# gt_cam_revf.net
KiCad netlist of a schematic drawn in EAGLE
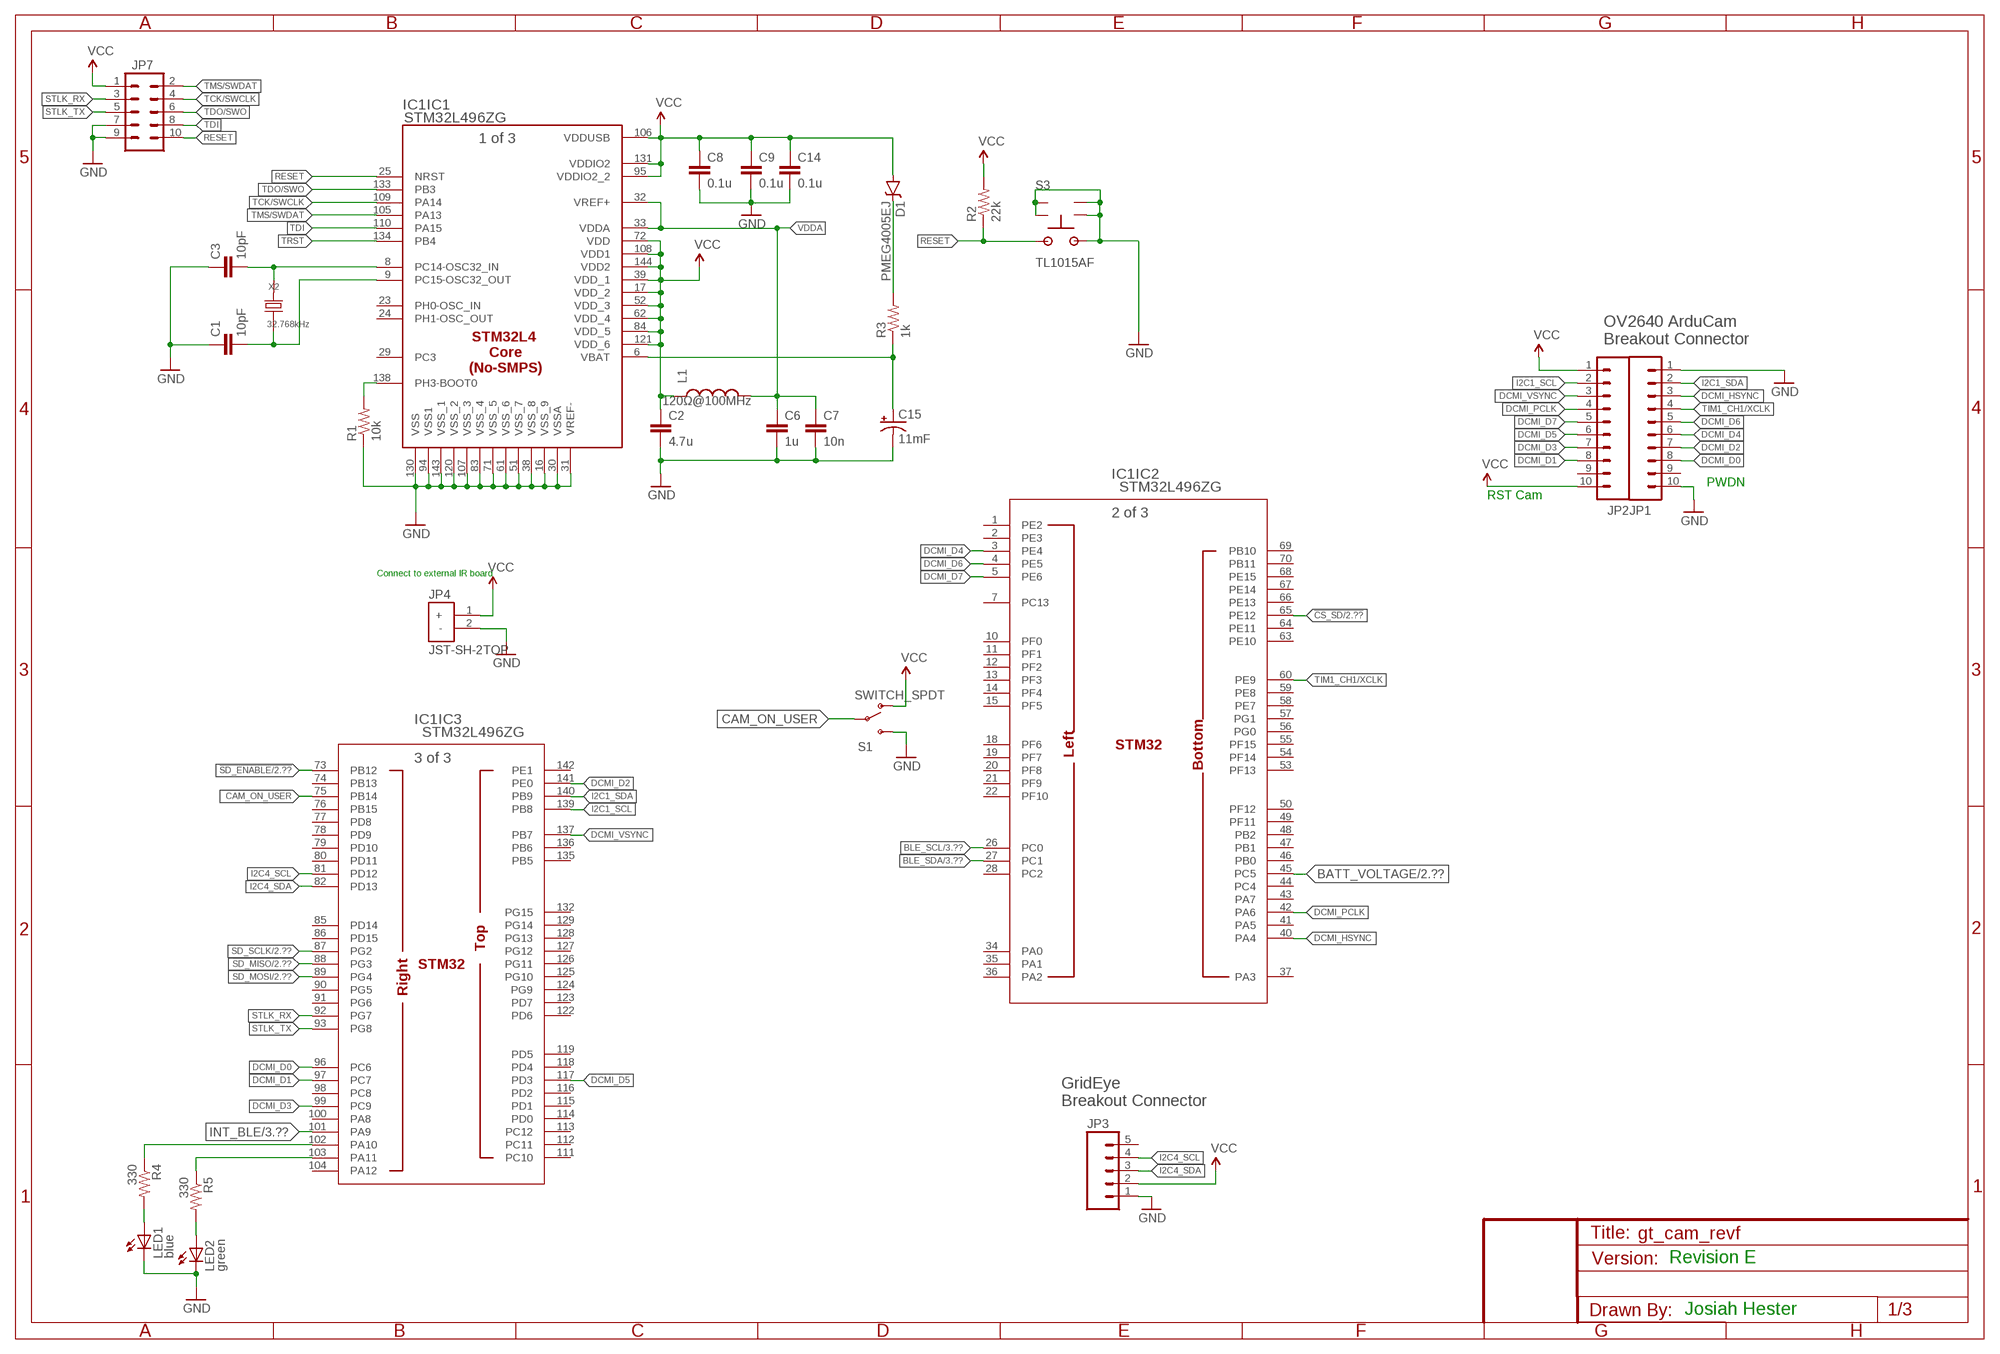
[diagram p0: schematic, sheet 1]
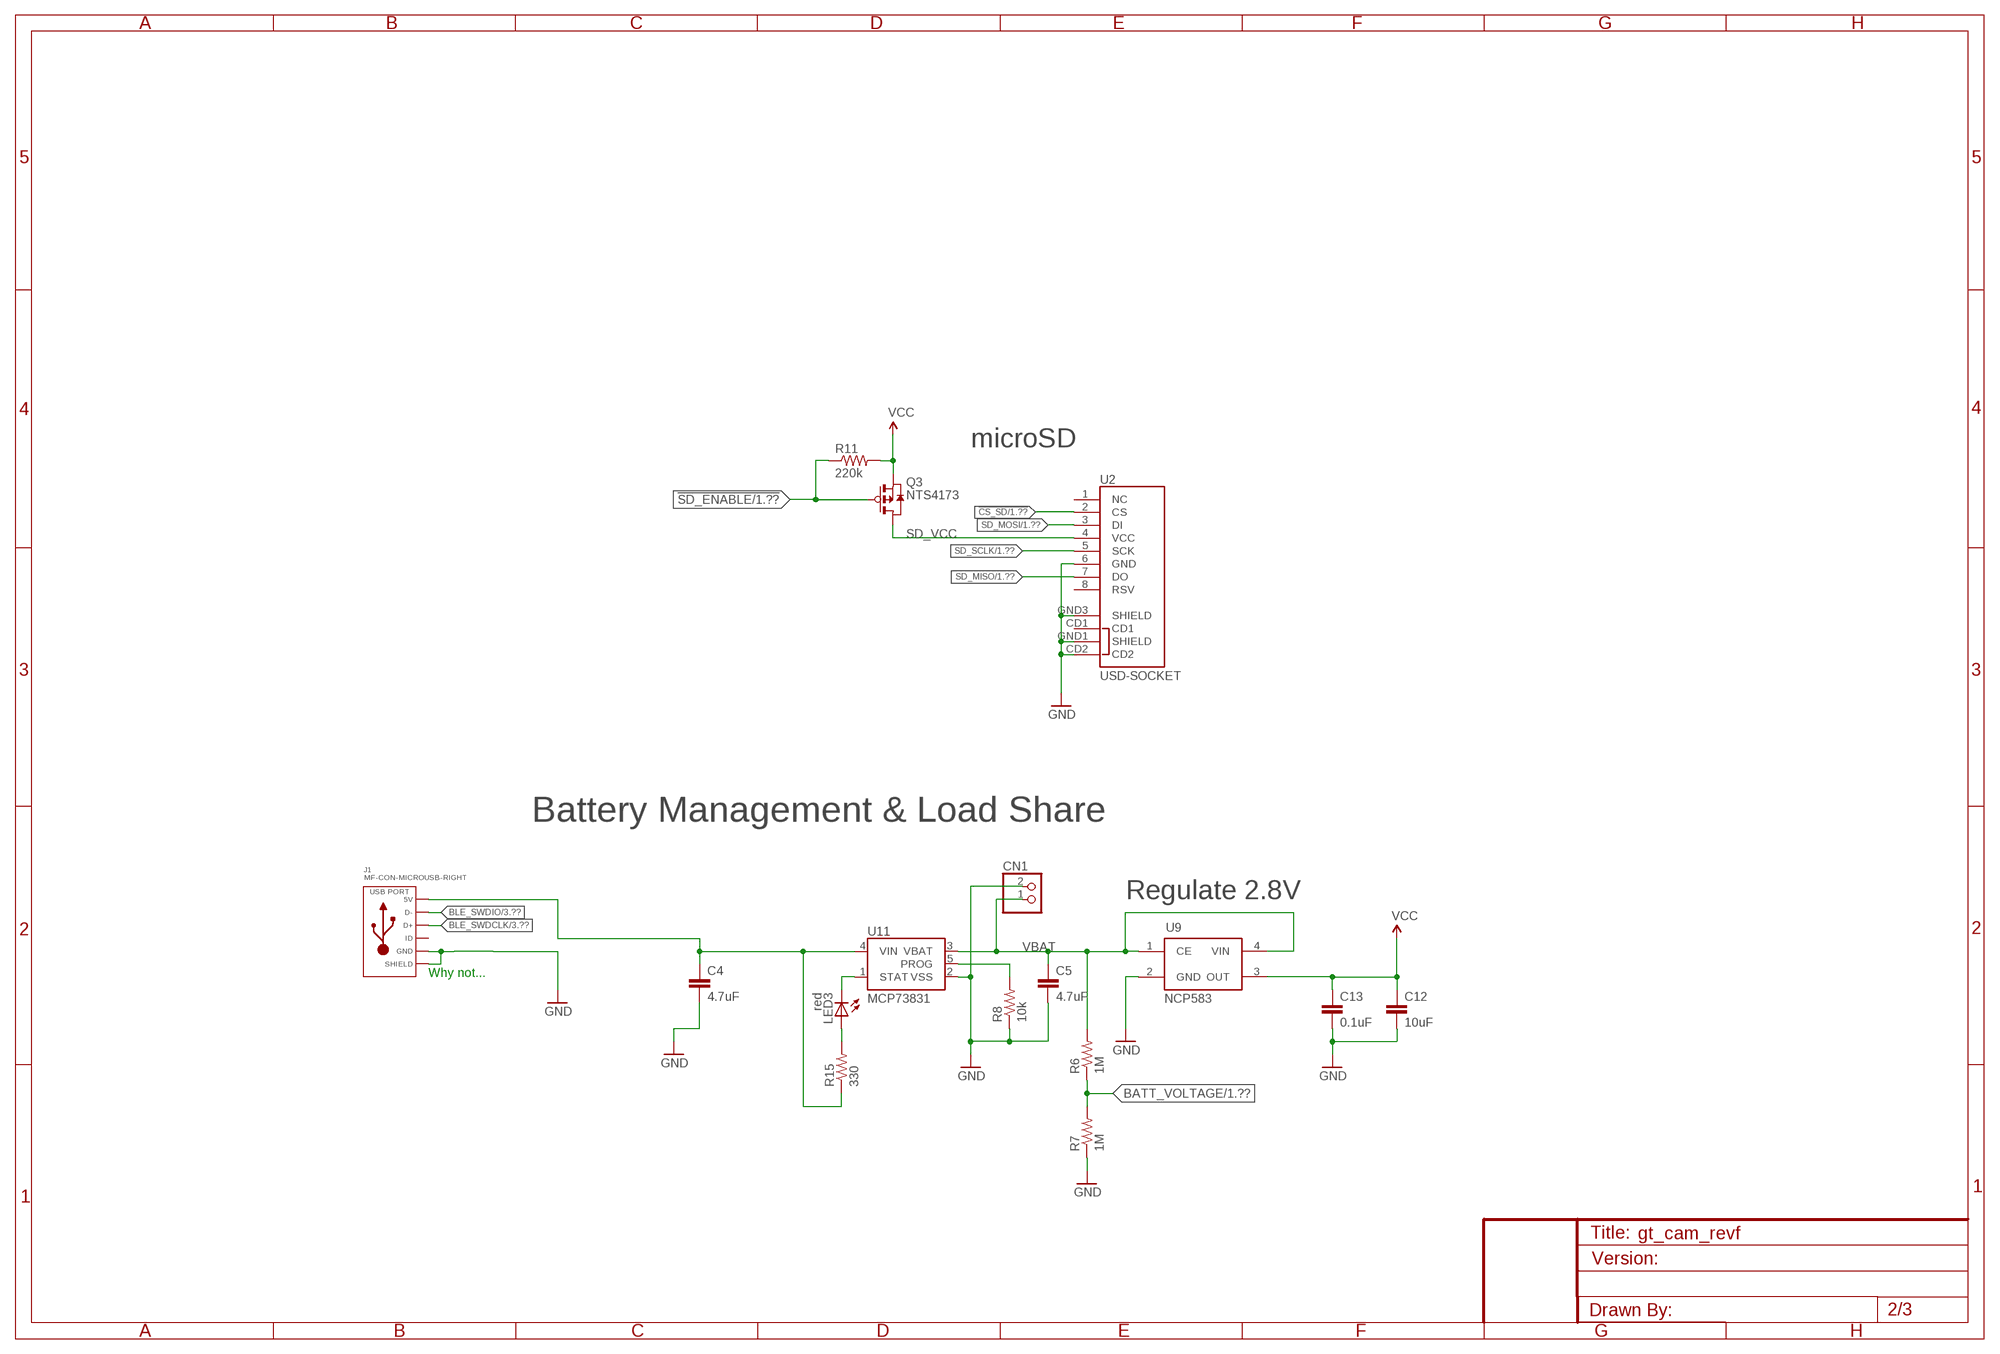
[diagram p1: schematic, sheet 2]
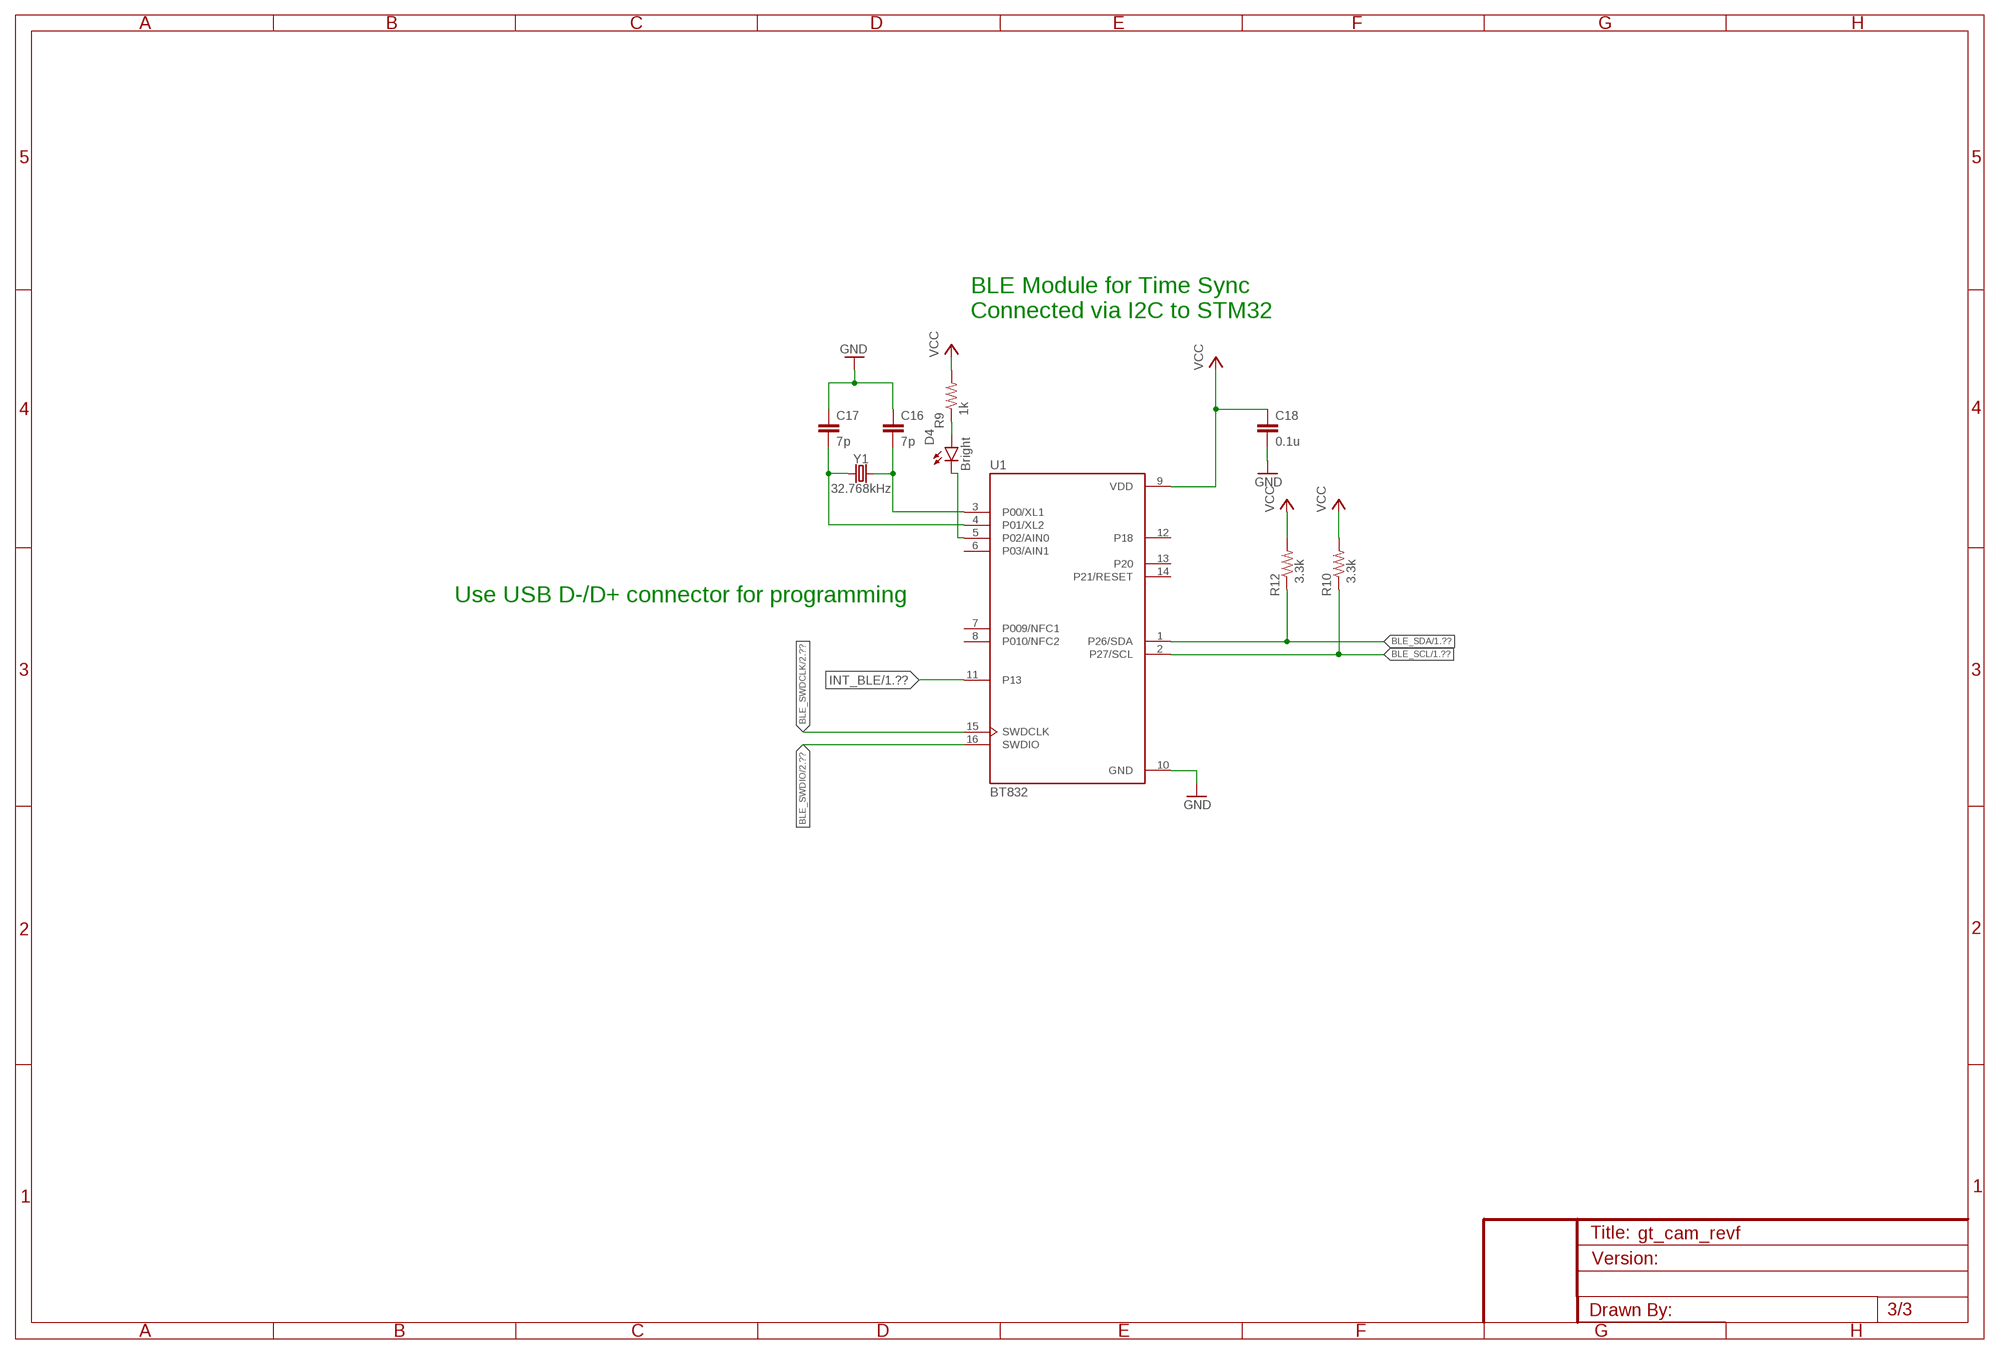
[diagram p2: schematic, sheet 3]

(export (version "E")
  (design (tool "Eeschema 10.0.6"))
  (components
    (comp (ref "C16")
      (value "7p")
      (footprint "eagle-import:0603")
      (libsource (lib "eagle-import") (part "C-EU0603"))
    )
    (comp (ref "C17")
      (value "7p")
      (footprint "eagle-import:0603")
      (libsource (lib "eagle-import") (part "C-EU0603"))
    )
    (comp (ref "C18")
      (value "0.1u")
      (footprint "eagle-import:0603")
      (libsource (lib "eagle-import") (part "C-EU0603"))
    )
    (comp (ref "D4")
      (value "Bright")
      (footprint "eagle-import:LED-0603")
      (libsource (lib "eagle-import") (part "necklace_done_LED0603"))
    )
    (comp (ref "R9")
      (value "1k")
      (footprint "eagle-import:0603")
      (libsource (lib "eagle-import") (part "R-EU0603"))
    )
    (comp (ref "R10")
      (value "3.3k")
      (footprint "eagle-import:0603")
      (libsource (lib "eagle-import") (part "R-EU0603"))
    )
    (comp (ref "R12")
      (value "3.3k")
      (footprint "eagle-import:0603")
      (libsource (lib "eagle-import") (part "R-EU0603"))
    )
    (comp (ref "U1")
      (value "BT832")
      (footprint "eagle-import:BLEMODULE_BT832")
      (fields (field (name "DIGI-KEY_PART_NUMBER") "1914-1013-1-ND") (field (name "MF") "Fanstel Corp."))
      (libsource (lib "eagle-import") (part "BT832"))
    )
    (comp (ref "Y1")
      (value "32.768kHz")
      (footprint "eagle-import:CRYSTAL-SMD-3.2X1.5MM")
      (fields (field (name "DIGI-KEY_PART_NUMBER") "SER4271CT-ND"))
      (libsource (lib "eagle-import") (part "CRYSTAL-32.768KHZSMD-3.2X1.5"))
    )
    (comp (ref "C4")
      (value "4.7uF")
      (footprint "eagle-import:0805")
      (libsource (lib "eagle-import") (part "CAP0805"))
    )
    (comp (ref "C5")
      (value "4.7uF")
      (footprint "eagle-import:0805")
      (libsource (lib "eagle-import") (part "CAP0805"))
    )
    (comp (ref "C12")
      (value "10uF")
      (footprint "eagle-import:0805")
      (libsource (lib "eagle-import") (part "CAP0805"))
    )
    (comp (ref "C13")
      (value "0.1uF")
      (footprint "eagle-import:0603")
      (libsource (lib "eagle-import") (part "C-EU0603"))
    )
    (comp (ref "CN1")
      (value "JST_2PIN-SMT-RA")
      (footprint "eagle-import:JST-PH-2-SMT-RA")
      (libsource (lib "eagle-import") (part "JST_2PIN-SMT-RA"))
    )
    (comp (ref "J1")
      (value "MF-CON-MICROUSB-RIGHT")
      (footprint "eagle-import:MICROUSB-RIGHT")
      (fields (field (name "HOUSEPART") "YES"))
      (libsource (lib "eagle-import") (part "USB_MICRO_RIGHT"))
    )
    (comp (ref "LED3")
      (value "red")
      (footprint "eagle-import:LED-0603")
      (libsource (lib "eagle-import") (part "LED0603"))
    )
    (comp (ref "Q3")
      (value "NTS4173")
      (footprint "eagle-import:SC-70-3")
      (libsource (lib "eagle-import") (part "NTS4173"))
    )
    (comp (ref "R6")
      (value "1M")
      (footprint "eagle-import:0603")
      (libsource (lib "eagle-import") (part "R-EU0603"))
    )
    (comp (ref "R7")
      (value "1M")
      (footprint "eagle-import:0603")
      (libsource (lib "eagle-import") (part "R-EU0603"))
    )
    (comp (ref "R8")
      (value "10k")
      (footprint "eagle-import:0603")
      (libsource (lib "eagle-import") (part "R-EU0603"))
    )
    (comp (ref "R11")
      (value "220k")
      (footprint "eagle-import:0603")
      (libsource (lib "eagle-import") (part "R-EU0603"))
    )
    (comp (ref "R15")
      (value "330")
      (footprint "eagle-import:0603")
      (libsource (lib "eagle-import") (part "R-EU0603"))
    )
    (comp (ref "U2")
      (value "USD-SOCKET")
      (footprint "eagle-import:MICROSD_1_1")
      (libsource (lib "eagle-import") (part "USD-SOCKET"))
    )
    (comp (ref "U9")
      (value "NCP583")
      (footprint "eagle-import:SC82-AB_1PRIMARY")
      (libsource (lib "eagle-import") (part "NCP583"))
    )
    (comp (ref "U11")
      (value "MCP73831")
      (footprint "eagle-import:SOT23-5")
      (libsource (lib "eagle-import") (part "MCP73831"))
    )
    (comp (ref "C1")
      (value "10pF")
      (footprint "eagle-import:0603")
      (libsource (lib "eagle-import") (part "C-EU0603"))
    )
    (comp (ref "C2")
      (value "4.7u")
      (footprint "eagle-import:0805")
      (libsource (lib "eagle-import") (part "CAP0805"))
    )
    (comp (ref "C3")
      (value "10pF")
      (footprint "eagle-import:0603")
      (libsource (lib "eagle-import") (part "C-EU0603"))
    )
    (comp (ref "C6")
      (value "1u")
      (footprint "eagle-import:0603")
      (libsource (lib "eagle-import") (part "C-EU0603"))
    )
    (comp (ref "C7")
      (value "10n")
      (footprint "eagle-import:0603")
      (libsource (lib "eagle-import") (part "C-EU0603"))
    )
    (comp (ref "C8")
      (value "0.1u")
      (footprint "eagle-import:0603")
      (libsource (lib "eagle-import") (part "C-EU0603"))
    )
    (comp (ref "C9")
      (value "0.1u")
      (footprint "eagle-import:0603")
      (libsource (lib "eagle-import") (part "C-EU0603"))
    )
    (comp (ref "C14")
      (value "0.1u")
      (footprint "eagle-import:0603")
      (libsource (lib "eagle-import") (part "C-EU0603"))
    )
    (comp (ref "C15")
      (value "11mF")
      (footprint "eagle-import:EIA3216")
      (libsource (lib "eagle-import") (part "CAP_POL1206"))
    )
    (comp (ref "D1")
      (value "PMEG4005EJ")
      (footprint "eagle-import:SOD-323")
      (libsource (lib "eagle-import") (part "DIODE-SCHOTTKY-PMEG4005EJ"))
    )
    (comp (ref "IC1")
      (value "STM32L496ZG")
      (footprint "eagle-import:LQFP144-20X20MM")
      (fields (field (name "DIGIKEY") "497-17999-ND"))
      (libsource (lib "eagle-import") (part "STM32L496ZG"))
    )
    (comp (ref "JP1")
      (value "M10SILK_FEMALE_PTH")
      (footprint "eagle-import:1X10")
      (libsource (lib "eagle-import") (part "M10SILK_FEMALE_PTH"))
    )
    (comp (ref "JP2")
      (value "M10SILK_FEMALE_PTH")
      (footprint "eagle-import:1X10")
      (libsource (lib "eagle-import") (part "M10SILK_FEMALE_PTH"))
    )
    (comp (ref "JP3")
      (value "M05LOCK")
      (footprint "eagle-import:1X05_LOCK")
      (libsource (lib "eagle-import") (part "M05LOCK"))
    )
    (comp (ref "JP4")
      (value "JST-SH-2TOP")
      (footprint "eagle-import:JST-SH-2-TOP")
      (libsource (lib "eagle-import") (part "JST-SH-2TOP"))
    )
    (comp (ref "JP7")
      (value "M05X21.27MM")
      (footprint "eagle-import:2X5_1.27MM")
      (libsource (lib "eagle-import") (part "M05X21.27MM"))
    )
    (comp (ref "L1")
      (value "120Ω@100MHz")
      (footprint "eagle-import:0402")
      (libsource (lib "eagle-import") (part "L-EU"))
    )
    (comp (ref "LED1")
      (value "blue")
      (footprint "eagle-import:LED-0603")
      (libsource (lib "eagle-import") (part "LED0603"))
    )
    (comp (ref "LED2")
      (value "green")
      (footprint "eagle-import:LED-0603")
      (libsource (lib "eagle-import") (part "LED0603"))
    )
    (comp (ref "R1")
      (value "10k")
      (footprint "eagle-import:0603")
      (libsource (lib "eagle-import") (part "R-EU0603"))
    )
    (comp (ref "R2")
      (value "22k")
      (footprint "eagle-import:0603")
      (libsource (lib "eagle-import") (part "R-EU0603"))
    )
    (comp (ref "R3")
      (value "1k")
      (footprint "eagle-import:0603")
      (libsource (lib "eagle-import") (part "R-EU0603"))
    )
    (comp (ref "R4")
      (value "330")
      (footprint "eagle-import:0603")
      (libsource (lib "eagle-import") (part "R-EU0603"))
    )
    (comp (ref "R5")
      (value "330")
      (footprint "eagle-import:0603")
      (libsource (lib "eagle-import") (part "R-EU0603"))
    )
    (comp (ref "S1")
      (value "SWITCH_SPDT")
      (footprint "eagle-import:EG-1213")
      (libsource (lib "eagle-import") (part "SWITCH_SPDT"))
    )
    (comp (ref "S3")
      (value "TL1015AF")
      (footprint "eagle-import:TS1015")
      (fields (field (name "MPN") "TL1015AF160QG"))
      (libsource (lib "eagle-import") (part "TL1015AF"))
    )
    (comp (ref "X2")
      (value "32.768kHz")
      (footprint "eagle-import:FC-135_1PRIMARY")
      (libsource (lib "eagle-import") (part "FC-135"))
    )
  )
  (nets
    (net (code "1") (name "BATT_VOLTAGE") (class "Default")
      (node (ref "IC1") (pin "45") (pinfunction "PC5_45") (pintype "bidirectional"))
      (node (ref "R6") (pin "1") (pinfunction "1_1") (pintype "passive"))
      (node (ref "R7") (pin "2") (pinfunction "2_2") (pintype "passive"))
    )
    (net (code "2") (name "BLE_SCL") (class "Default")
      (node (ref "IC1") (pin "26") (pinfunction "PC0_26") (pintype "bidirectional"))
      (node (ref "R10") (pin "1") (pinfunction "1_1") (pintype "passive"))
      (node (ref "U1") (pin "2") (pinfunction "P27/SCL_2") (pintype "bidirectional"))
    )
    (net (code "3") (name "BLE_SDA") (class "Default")
      (node (ref "IC1") (pin "27") (pinfunction "PC1_27") (pintype "bidirectional"))
      (node (ref "R12") (pin "1") (pinfunction "1_1") (pintype "passive"))
      (node (ref "U1") (pin "1") (pinfunction "P26/SDA_1") (pintype "bidirectional"))
    )
    (net (code "4") (name "BLE_SWDCLK") (class "Default")
      (node (ref "J1") (pin "3") (pinfunction "D+_3") (pintype "bidirectional"))
      (node (ref "U1") (pin "15") (pinfunction "SWDCLK_15") (pintype "input"))
    )
    (net (code "5") (name "BLE_SWDIO") (class "Default")
      (node (ref "J1") (pin "2") (pinfunction "D-_2") (pintype "bidirectional"))
      (node (ref "U1") (pin "16") (pinfunction "SWDIO_16") (pintype "bidirectional"))
    )
    (net (code "6") (name "CAM_ON_USER") (class "Default")
      (node (ref "IC1") (pin "75") (pinfunction "PB14_75") (pintype "bidirectional"))
      (node (ref "S1") (pin "C") (pinfunction "C_C") (pintype "passive"))
    )
    (net (code "7") (name "DCMI_D0") (class "Default")
      (node (ref "IC1") (pin "96") (pinfunction "PC6_96") (pintype "bidirectional"))
      (node (ref "JP1") (pin "8") (pinfunction "8_8") (pintype "passive"))
    )
    (net (code "8") (name "DCMI_D1") (class "Default")
      (node (ref "IC1") (pin "97") (pinfunction "PC7_97") (pintype "bidirectional"))
      (node (ref "JP2") (pin "8") (pinfunction "8_8") (pintype "passive"))
    )
    (net (code "9") (name "DCMI_D2") (class "Default")
      (node (ref "IC1") (pin "141") (pinfunction "PE0_141") (pintype "bidirectional"))
      (node (ref "JP1") (pin "7") (pinfunction "7_7") (pintype "passive"))
    )
    (net (code "10") (name "DCMI_D3") (class "Default")
      (node (ref "IC1") (pin "99") (pinfunction "PC9_99") (pintype "bidirectional"))
      (node (ref "JP2") (pin "7") (pinfunction "7_7") (pintype "passive"))
    )
    (net (code "11") (name "DCMI_D4") (class "Default")
      (node (ref "IC1") (pin "3") (pinfunction "PE4_3") (pintype "bidirectional"))
      (node (ref "JP1") (pin "6") (pinfunction "6_6") (pintype "passive"))
    )
    (net (code "12") (name "DCMI_D5") (class "Default")
      (node (ref "IC1") (pin "117") (pinfunction "PD3_117") (pintype "bidirectional"))
      (node (ref "JP2") (pin "6") (pinfunction "6_6") (pintype "passive"))
    )
    (net (code "13") (name "DCMI_D6") (class "Default")
      (node (ref "IC1") (pin "4") (pinfunction "PE5_4") (pintype "bidirectional"))
      (node (ref "JP1") (pin "5") (pinfunction "5_5") (pintype "passive"))
    )
    (net (code "14") (name "DCMI_D7") (class "Default")
      (node (ref "IC1") (pin "5") (pinfunction "PE6_5") (pintype "bidirectional"))
      (node (ref "JP2") (pin "5") (pinfunction "5_5") (pintype "passive"))
    )
    (net (code "15") (name "DCMI_HSYNC") (class "Default")
      (node (ref "IC1") (pin "40") (pinfunction "PA4_40") (pintype "bidirectional"))
      (node (ref "JP1") (pin "3") (pinfunction "3_3") (pintype "passive"))
    )
    (net (code "16") (name "DCMI_PCLK") (class "Default")
      (node (ref "IC1") (pin "42") (pinfunction "PA6_42") (pintype "bidirectional"))
      (node (ref "JP2") (pin "4") (pinfunction "4_4") (pintype "passive"))
    )
    (net (code "17") (name "DCMI_VSYNC") (class "Default")
      (node (ref "IC1") (pin "137") (pinfunction "PB7_137") (pintype "bidirectional"))
      (node (ref "JP2") (pin "3") (pinfunction "3_3") (pintype "passive"))
    )
    (net (code "18") (name "GND") (class "Default")
      (node (ref "C1") (pin "1") (pinfunction "1_1") (pintype "passive"))
      (node (ref "C12") (pin "2") (pinfunction "2_2") (pintype "passive"))
      (node (ref "C13") (pin "2") (pinfunction "2_2") (pintype "passive"))
      (node (ref "C14") (pin "2") (pinfunction "2_2") (pintype "passive"))
      (node (ref "C15") (pin "C") (pinfunction "-_C") (pintype "passive"))
      (node (ref "C16") (pin "1") (pinfunction "1_1") (pintype "passive"))
      (node (ref "C17") (pin "1") (pinfunction "1_1") (pintype "passive"))
      (node (ref "C18") (pin "2") (pinfunction "2_2") (pintype "passive"))
      (node (ref "C2") (pin "2") (pinfunction "2_2") (pintype "passive"))
      (node (ref "C3") (pin "1") (pinfunction "1_1") (pintype "passive"))
      (node (ref "C4") (pin "2") (pinfunction "2_2") (pintype "passive"))
      (node (ref "C5") (pin "2") (pinfunction "2_2") (pintype "passive"))
      (node (ref "C6") (pin "2") (pinfunction "2_2") (pintype "passive"))
      (node (ref "C7") (pin "2") (pinfunction "2_2") (pintype "passive"))
      (node (ref "C8") (pin "2") (pinfunction "2_2") (pintype "passive"))
      (node (ref "C9") (pin "2") (pinfunction "2_2") (pintype "passive"))
      (node (ref "CN1") (pin "2") (pinfunction "1_2") (pintype "passive"))
      (node (ref "IC1") (pin "107") (pinfunction "VSS_3_107") (pintype "power_in"))
      (node (ref "IC1") (pin "120") (pinfunction "VSS_2_120") (pintype "power_in"))
      (node (ref "IC1") (pin "130") (pinfunction "VSS_130") (pintype "power_in"))
      (node (ref "IC1") (pin "143") (pinfunction "VSS_1_143") (pintype "power_in"))
      (node (ref "IC1") (pin "16") (pinfunction "VSS_9_16") (pintype "power_in"))
      (node (ref "IC1") (pin "30") (pinfunction "VSSA_30") (pintype "power_in"))
      (node (ref "IC1") (pin "31") (pinfunction "VREF-_31") (pintype "power_in"))
      (node (ref "IC1") (pin "38") (pinfunction "VSS_8_38") (pintype "power_in"))
      (node (ref "IC1") (pin "51") (pinfunction "VSS_7_51") (pintype "power_in"))
      (node (ref "IC1") (pin "61") (pinfunction "VSS_6_61") (pintype "power_in"))
      (node (ref "IC1") (pin "71") (pinfunction "VSS_5_71") (pintype "power_in"))
      (node (ref "IC1") (pin "83") (pinfunction "VSS_4_83") (pintype "power_in"))
      (node (ref "IC1") (pin "94") (pinfunction "VSS1_94") (pintype "power_in"))
      (node (ref "J1") (pin "5") (pinfunction "GND_5") (pintype "power_in"))
      (node (ref "J1") (pin "S1") (pinfunction "SLD_S1") (pintype "power_in"))
      (node (ref "J1") (pin "S2") (pinfunction "SLD_S2") (pintype "power_in"))
      (node (ref "J1") (pin "S3") (pinfunction "SLD_S3") (pintype "power_in"))
      (node (ref "J1") (pin "S4") (pinfunction "SLD_S4") (pintype "power_in"))
      (node (ref "J1") (pin "S5") (pinfunction "SLD_S5") (pintype "power_in"))
      (node (ref "J1") (pin "S6") (pinfunction "SLD_S6") (pintype "power_in"))
      (node (ref "JP1") (pin "1") (pinfunction "1_1") (pintype "passive"))
      (node (ref "JP1") (pin "10") (pinfunction "10_10") (pintype "passive"))
      (node (ref "JP3") (pin "1") (pinfunction "1_1") (pintype "passive"))
      (node (ref "JP4") (pin "2") (pinfunction "-_2") (pintype "bidirectional"))
      (node (ref "JP7") (pin "7") (pinfunction "7_7") (pintype "passive"))
      (node (ref "JP7") (pin "9") (pinfunction "9_9") (pintype "passive"))
      (node (ref "LED1") (pin "C") (pinfunction "C_C") (pintype "passive"))
      (node (ref "LED2") (pin "C") (pinfunction "C_C") (pintype "passive"))
      (node (ref "R1") (pin "1") (pinfunction "1_1") (pintype "passive"))
      (node (ref "R7") (pin "1") (pinfunction "1_1") (pintype "passive"))
      (node (ref "R8") (pin "1") (pinfunction "1_1") (pintype "passive"))
      (node (ref "S1") (pin "S") (pinfunction "S_S") (pintype "passive"))
      (node (ref "S3") (pin "1") (pinfunction "1_1") (pintype "bidirectional"))
      (node (ref "S3") (pin "G1") (pinfunction "GND_G1") (pintype "bidirectional"))
      (node (ref "S3") (pin "G2") (pinfunction "GND_G2") (pintype "bidirectional"))
      (node (ref "S3") (pin "G3") (pinfunction "GND_G3") (pintype "bidirectional"))
      (node (ref "S3") (pin "G4") (pinfunction "GND_G4") (pintype "bidirectional"))
      (node (ref "U1") (pin "10") (pinfunction "GND_10") (pintype "power_in"))
      (node (ref "U11") (pin "2") (pinfunction "VSS_2") (pintype "power_in"))
      (node (ref "U2") (pin "6") (pinfunction "GND_6") (pintype "bidirectional"))
      (node (ref "U2") (pin "CD2") (pinfunction "CD2_CD2") (pintype "bidirectional"))
      (node (ref "U2") (pin "GND1") (pinfunction "SHIELD_GND1") (pintype "bidirectional"))
      (node (ref "U2") (pin "GND3") (pinfunction "SHIELD_GND3") (pintype "bidirectional"))
      (node (ref "U9") (pin "2") (pinfunction "GND_2") (pintype "bidirectional"))
    )
    (net (code "19") (name "I2C1_SCL") (class "Default")
      (node (ref "IC1") (pin "139") (pinfunction "PB8_139") (pintype "bidirectional"))
      (node (ref "JP2") (pin "2") (pinfunction "2_2") (pintype "passive"))
    )
    (net (code "20") (name "I2C1_SDA") (class "Default")
      (node (ref "IC1") (pin "140") (pinfunction "PB9_140") (pintype "bidirectional"))
      (node (ref "JP1") (pin "2") (pinfunction "2_2") (pintype "passive"))
    )
    (net (code "21") (name "I2C4_SCL") (class "Default")
      (node (ref "IC1") (pin "81") (pinfunction "PD12_81") (pintype "bidirectional"))
      (node (ref "JP3") (pin "4") (pinfunction "4_4") (pintype "passive"))
    )
    (net (code "22") (name "I2C4_SDA") (class "Default")
      (node (ref "IC1") (pin "82") (pinfunction "PD13_82") (pintype "bidirectional"))
      (node (ref "JP3") (pin "3") (pinfunction "3_3") (pintype "passive"))
    )
    (net (code "23") (name "INT_BLE") (class "Default")
      (node (ref "IC1") (pin "101") (pinfunction "PA9_101") (pintype "bidirectional"))
      (node (ref "U1") (pin "11") (pinfunction "P13_11") (pintype "bidirectional"))
    )
    (net (code "24") (name "Net-(C15-+)") (class "Default")
      (node (ref "C15") (pin "A") (pinfunction "+_A") (pintype "passive"))
      (node (ref "IC1") (pin "6") (pinfunction "VBAT_6") (pintype "power_in"))
      (node (ref "R3") (pin "1") (pinfunction "1_1") (pintype "passive"))
    )
    (net (code "25") (name "Net-(D1-PadC)") (class "Default")
      (node (ref "D1") (pin "C") (pinfunction "C_C") (pintype "passive"))
      (node (ref "R3") (pin "2") (pinfunction "2_2") (pintype "passive"))
    )
    (net (code "26") (name "Net-(D4-PadA)") (class "Default")
      (node (ref "D4") (pin "A") (pinfunction "A_A") (pintype "passive"))
      (node (ref "R9") (pin "1") (pinfunction "1_1") (pintype "passive"))
    )
    (net (code "27") (name "Net-(IC1A-PC14-OSC32_IN)") (class "Default")
      (node (ref "C3") (pin "2") (pinfunction "2_2") (pintype "passive"))
      (node (ref "IC1") (pin "8") (pinfunction "PC14-OSC32_IN_8") (pintype "bidirectional"))
      (node (ref "X2") (pin "2") (pinfunction "2_2") (pintype "bidirectional"))
    )
    (net (code "28") (name "Net-(IC1A-PC15-OSC32_OUT)") (class "Default")
      (node (ref "C1") (pin "2") (pinfunction "2_2") (pintype "passive"))
      (node (ref "IC1") (pin "9") (pinfunction "PC15-OSC32_OUT_9") (pintype "bidirectional"))
      (node (ref "X2") (pin "1") (pinfunction "1_1") (pintype "bidirectional"))
    )
    (net (code "29") (name "Net-(IC1A-PH3-BOOT0)") (class "Default")
      (node (ref "IC1") (pin "138") (pinfunction "PH3-BOOT0_138") (pintype "bidirectional"))
      (node (ref "R1") (pin "2") (pinfunction "2_2") (pintype "passive"))
    )
    (net (code "30") (name "Net-(IC1C-PA10)") (class "Default")
      (node (ref "IC1") (pin "102") (pinfunction "PA10_102") (pintype "bidirectional"))
      (node (ref "R4") (pin "1") (pinfunction "1_1") (pintype "passive"))
    )
    (net (code "31") (name "Net-(IC1C-PA11)") (class "Default")
      (node (ref "IC1") (pin "103") (pinfunction "PA11_103") (pintype "bidirectional"))
      (node (ref "R5") (pin "1") (pinfunction "1_1") (pintype "passive"))
    )
    (net (code "32") (name "Net-(J1-5V)") (class "Default")
      (node (ref "C4") (pin "1") (pinfunction "1_1") (pintype "passive"))
      (node (ref "J1") (pin "1") (pinfunction "5V_1") (pintype "power_in"))
      (node (ref "R15") (pin "1") (pinfunction "1_1") (pintype "passive"))
      (node (ref "U11") (pin "4") (pinfunction "VIN_4") (pintype "power_in"))
    )
    (net (code "33") (name "Net-(LED1-PadA)") (class "Default")
      (node (ref "LED1") (pin "A") (pinfunction "A_A") (pintype "passive"))
      (node (ref "R4") (pin "2") (pinfunction "2_2") (pintype "passive"))
    )
    (net (code "34") (name "Net-(LED2-PadA)") (class "Default")
      (node (ref "LED2") (pin "A") (pinfunction "A_A") (pintype "passive"))
      (node (ref "R5") (pin "2") (pinfunction "2_2") (pintype "passive"))
    )
    (net (code "35") (name "Net-(LED3-PadA)") (class "Default")
      (node (ref "LED3") (pin "A") (pinfunction "A_A") (pintype "passive"))
      (node (ref "R15") (pin "2") (pinfunction "2_2") (pintype "passive"))
    )
    (net (code "36") (name "Net-(U1-P00{slash}XL1)") (class "Default")
      (node (ref "C16") (pin "2") (pinfunction "2_2") (pintype "passive"))
      (node (ref "U1") (pin "3") (pinfunction "P00/XL1_3") (pintype "bidirectional"))
      (node (ref "Y1") (pin "P$2") (pinfunction "2_P$2") (pintype "passive"))
    )
    (net (code "37") (name "Net-(U1-P01{slash}XL2)") (class "Default")
      (node (ref "C17") (pin "2") (pinfunction "2_2") (pintype "passive"))
      (node (ref "U1") (pin "4") (pinfunction "P01/XL2_4") (pintype "bidirectional"))
      (node (ref "Y1") (pin "P$1") (pinfunction "1_P$1") (pintype "passive"))
    )
    (net (code "38") (name "Net-(U1-P02{slash}AIN0)") (class "Default")
      (node (ref "D4") (pin "C") (pinfunction "C_C") (pintype "passive"))
      (node (ref "U1") (pin "5") (pinfunction "P02/AIN0_5") (pintype "bidirectional"))
    )
    (net (code "39") (name "Net-(U11-PROG)") (class "Default")
      (node (ref "R8") (pin "2") (pinfunction "2_2") (pintype "passive"))
      (node (ref "U11") (pin "5") (pinfunction "PROG_5") (pintype "input"))
    )
    (net (code "40") (name "Net-(U11-STAT)") (class "Default")
      (node (ref "LED3") (pin "C") (pinfunction "C_C") (pintype "passive"))
      (node (ref "U11") (pin "1") (pinfunction "STAT_1") (pintype "output"))
    )
    (net (code "41") (name "RESET") (class "Default")
      (node (ref "IC1") (pin "25") (pinfunction "NRST_25") (pintype "bidirectional"))
      (node (ref "JP7") (pin "10") (pinfunction "10_10") (pintype "passive"))
      (node (ref "R2") (pin "1") (pinfunction "1_1") (pintype "passive"))
      (node (ref "S3") (pin "2") (pinfunction "2_2") (pintype "bidirectional"))
    )
    (net (code "42") (name "SD_MISO") (class "Default")
      (node (ref "IC1") (pin "88") (pinfunction "PG3_88") (pintype "bidirectional"))
      (node (ref "U2") (pin "7") (pinfunction "DO_7") (pintype "bidirectional"))
    )
    (net (code "43") (name "SD_MOSI") (class "Default")
      (node (ref "IC1") (pin "89") (pinfunction "PG4_89") (pintype "bidirectional"))
      (node (ref "U2") (pin "3") (pinfunction "DI_3") (pintype "bidirectional"))
    )
    (net (code "44") (name "SD_SCLK") (class "Default")
      (node (ref "IC1") (pin "87") (pinfunction "PG2_87") (pintype "bidirectional"))
      (node (ref "U2") (pin "5") (pinfunction "SCK_5") (pintype "bidirectional"))
    )
    (net (code "45") (name "SD_VCC") (class "Default")
      (node (ref "Q3") (pin "P3") (pinfunction "D_P3") (pintype "passive"))
      (node (ref "U2") (pin "4") (pinfunction "VCC_4") (pintype "bidirectional"))
    )
    (net (code "46") (name "STLK_RX") (class "Default")
      (node (ref "IC1") (pin "92") (pinfunction "PG7_92") (pintype "bidirectional"))
      (node (ref "JP7") (pin "3") (pinfunction "3_3") (pintype "passive"))
    )
    (net (code "47") (name "STLK_TX") (class "Default")
      (node (ref "IC1") (pin "93") (pinfunction "PG8_93") (pintype "bidirectional"))
      (node (ref "JP7") (pin "5") (pinfunction "5_5") (pintype "passive"))
    )
    (net (code "48") (name "TCK{slash}SWCLK") (class "Default")
      (node (ref "IC1") (pin "109") (pinfunction "PA14_109") (pintype "bidirectional"))
      (node (ref "JP7") (pin "4") (pinfunction "4_4") (pintype "passive"))
    )
    (net (code "49") (name "TDI") (class "Default")
      (node (ref "IC1") (pin "110") (pinfunction "PA15_110") (pintype "bidirectional"))
      (node (ref "JP7") (pin "8") (pinfunction "8_8") (pintype "passive"))
    )
    (net (code "50") (name "TDO{slash}SWO") (class "Default")
      (node (ref "IC1") (pin "133") (pinfunction "PB3_133") (pintype "bidirectional"))
      (node (ref "JP7") (pin "6") (pinfunction "6_6") (pintype "passive"))
    )
    (net (code "51") (name "TIM1_CH1{slash}XCLK") (class "Default")
      (node (ref "IC1") (pin "60") (pinfunction "PE9_60") (pintype "bidirectional"))
      (node (ref "JP1") (pin "4") (pinfunction "4_4") (pintype "passive"))
    )
    (net (code "52") (name "TMS{slash}SWDAT") (class "Default")
      (node (ref "IC1") (pin "105") (pinfunction "PA13_105") (pintype "bidirectional"))
      (node (ref "JP7") (pin "2") (pinfunction "2_2") (pintype "passive"))
    )
    (net (code "53") (name "TRST") (class "Default")
      (node (ref "IC1") (pin "134") (pinfunction "PB4_134") (pintype "bidirectional"))
    )
    (net (code "54") (name "VBAT") (class "Default")
      (node (ref "C5") (pin "1") (pinfunction "1_1") (pintype "passive"))
      (node (ref "CN1") (pin "1") (pinfunction "2_1") (pintype "passive"))
      (node (ref "R6") (pin "2") (pinfunction "2_2") (pintype "passive"))
      (node (ref "U11") (pin "3") (pinfunction "VBAT_3") (pintype "power_in"))
      (node (ref "U9") (pin "1") (pinfunction "CE_1") (pintype "bidirectional"))
      (node (ref "U9") (pin "4") (pinfunction "VIN_4") (pintype "bidirectional"))
    )
    (net (code "55") (name "VCC") (class "Default")
      (node (ref "C12") (pin "1") (pinfunction "1_1") (pintype "passive"))
      (node (ref "C13") (pin "1") (pinfunction "1_1") (pintype "passive"))
      (node (ref "C14") (pin "1") (pinfunction "1_1") (pintype "passive"))
      (node (ref "C18") (pin "1") (pinfunction "1_1") (pintype "passive"))
      (node (ref "C2") (pin "1") (pinfunction "1_1") (pintype "passive"))
      (node (ref "C8") (pin "1") (pinfunction "1_1") (pintype "passive"))
      (node (ref "C9") (pin "1") (pinfunction "1_1") (pintype "passive"))
      (node (ref "D1") (pin "A") (pinfunction "A_A") (pintype "passive"))
      (node (ref "IC1") (pin "106") (pinfunction "VDDUSB_106") (pintype "power_in"))
      (node (ref "IC1") (pin "108") (pinfunction "VDD1_108") (pintype "power_in"))
      (node (ref "IC1") (pin "121") (pinfunction "VDD_6_121") (pintype "power_in"))
      (node (ref "IC1") (pin "131") (pinfunction "VDDIO2_131") (pintype "power_in"))
      (node (ref "IC1") (pin "144") (pinfunction "VDD2_144") (pintype "power_in"))
      (node (ref "IC1") (pin "17") (pinfunction "VDD_2_17") (pintype "power_in"))
      (node (ref "IC1") (pin "39") (pinfunction "VDD_1_39") (pintype "power_in"))
      (node (ref "IC1") (pin "52") (pinfunction "VDD_3_52") (pintype "power_in"))
      (node (ref "IC1") (pin "62") (pinfunction "VDD_4_62") (pintype "power_in"))
      (node (ref "IC1") (pin "72") (pinfunction "VDD_72") (pintype "power_in"))
      (node (ref "IC1") (pin "84") (pinfunction "VDD_5_84") (pintype "power_in"))
      (node (ref "IC1") (pin "95") (pinfunction "VDDIO2_2_95") (pintype "power_in"))
      (node (ref "JP2") (pin "1") (pinfunction "1_1") (pintype "passive"))
      (node (ref "JP2") (pin "10") (pinfunction "10_10") (pintype "passive"))
      (node (ref "JP3") (pin "2") (pinfunction "2_2") (pintype "passive"))
      (node (ref "JP4") (pin "1") (pinfunction "+_1") (pintype "bidirectional"))
      (node (ref "JP7") (pin "1") (pinfunction "1_1") (pintype "passive"))
      (node (ref "L1") (pin "1") (pinfunction "1_1") (pintype "passive"))
      (node (ref "Q3") (pin "P2") (pinfunction "S_P2") (pintype "passive"))
      (node (ref "R10") (pin "2") (pinfunction "2_2") (pintype "passive"))
      (node (ref "R11") (pin "2") (pinfunction "2_2") (pintype "passive"))
      (node (ref "R12") (pin "2") (pinfunction "2_2") (pintype "passive"))
      (node (ref "R2") (pin "2") (pinfunction "2_2") (pintype "passive"))
      (node (ref "R9") (pin "2") (pinfunction "2_2") (pintype "passive"))
      (node (ref "S1") (pin "P") (pinfunction "O_P") (pintype "passive"))
      (node (ref "U1") (pin "9") (pinfunction "VDD_9") (pintype "power_in"))
      (node (ref "U9") (pin "3") (pinfunction "OUT_3") (pintype "bidirectional"))
    )
    (net (code "56") (name "VDDA") (class "Default")
      (node (ref "C6") (pin "1") (pinfunction "1_1") (pintype "passive"))
      (node (ref "C7") (pin "1") (pinfunction "1_1") (pintype "passive"))
      (node (ref "IC1") (pin "32") (pinfunction "VREF+_32") (pintype "power_in"))
      (node (ref "IC1") (pin "33") (pinfunction "VDDA_33") (pintype "power_in"))
      (node (ref "L1") (pin "2") (pinfunction "2_2") (pintype "passive"))
    )
    (net (code "57") (name "unconnected-(IC1A-PC3-Pad29)") (class "Default")
      (node (ref "IC1") (pin "29") (pinfunction "PC3_29") (pintype "bidirectional"))
    )
    (net (code "58") (name "unconnected-(IC1A-PH0-OSC_IN-Pad23)") (class "Default")
      (node (ref "IC1") (pin "23") (pinfunction "PH0-OSC_IN_23") (pintype "bidirectional"))
    )
    (net (code "59") (name "unconnected-(IC1A-PH1-OSC_OUT-Pad24)") (class "Default")
      (node (ref "IC1") (pin "24") (pinfunction "PH1-OSC_OUT_24") (pintype "bidirectional"))
    )
    (net (code "60") (name "unconnected-(IC1B-PA0-Pad34)") (class "Default")
      (node (ref "IC1") (pin "34") (pinfunction "PA0_34") (pintype "bidirectional"))
    )
    (net (code "61") (name "unconnected-(IC1B-PA1-Pad35)") (class "Default")
      (node (ref "IC1") (pin "35") (pinfunction "PA1_35") (pintype "bidirectional"))
    )
    (net (code "62") (name "unconnected-(IC1B-PA2-Pad36)") (class "Default")
      (node (ref "IC1") (pin "36") (pinfunction "PA2_36") (pintype "bidirectional"))
    )
    (net (code "63") (name "unconnected-(IC1B-PA3-Pad37)") (class "Default")
      (node (ref "IC1") (pin "37") (pinfunction "PA3_37") (pintype "bidirectional"))
    )
    (net (code "64") (name "unconnected-(IC1B-PA5-Pad41)") (class "Default")
      (node (ref "IC1") (pin "41") (pinfunction "PA5_41") (pintype "bidirectional"))
    )
    (net (code "65") (name "unconnected-(IC1B-PA7-Pad43)") (class "Default")
      (node (ref "IC1") (pin "43") (pinfunction "PA7_43") (pintype "bidirectional"))
    )
    (net (code "66") (name "unconnected-(IC1B-PB0-Pad46)") (class "Default")
      (node (ref "IC1") (pin "46") (pinfunction "PB0_46") (pintype "bidirectional"))
    )
    (net (code "67") (name "unconnected-(IC1B-PB1-Pad47)") (class "Default")
      (node (ref "IC1") (pin "47") (pinfunction "PB1_47") (pintype "bidirectional"))
    )
    (net (code "68") (name "unconnected-(IC1B-PB2-Pad48)") (class "Default")
      (node (ref "IC1") (pin "48") (pinfunction "PB2_48") (pintype "bidirectional"))
    )
    (net (code "69") (name "unconnected-(IC1B-PB10-Pad69)") (class "Default")
      (node (ref "IC1") (pin "69") (pinfunction "PB10_69") (pintype "bidirectional"))
    )
    (net (code "70") (name "unconnected-(IC1B-PB11-Pad70)") (class "Default")
      (node (ref "IC1") (pin "70") (pinfunction "PB11_70") (pintype "bidirectional"))
    )
    (net (code "71") (name "unconnected-(IC1B-PC2-Pad28)") (class "Default")
      (node (ref "IC1") (pin "28") (pinfunction "PC2_28") (pintype "bidirectional"))
    )
    (net (code "72") (name "unconnected-(IC1B-PC4-Pad44)") (class "Default")
      (node (ref "IC1") (pin "44") (pinfunction "PC4_44") (pintype "bidirectional"))
    )
    (net (code "73") (name "unconnected-(IC1B-PC13-Pad7)") (class "Default")
      (node (ref "IC1") (pin "7") (pinfunction "PC13_7") (pintype "bidirectional"))
    )
    (net (code "74") (name "unconnected-(IC1B-PE2-Pad1)") (class "Default")
      (node (ref "IC1") (pin "1") (pinfunction "PE2_1") (pintype "bidirectional"))
    )
    (net (code "75") (name "unconnected-(IC1B-PE3-Pad2)") (class "Default")
      (node (ref "IC1") (pin "2") (pinfunction "PE3_2") (pintype "bidirectional"))
    )
    (net (code "76") (name "unconnected-(IC1B-PE7-Pad58)") (class "Default")
      (node (ref "IC1") (pin "58") (pinfunction "PE7_58") (pintype "bidirectional"))
    )
    (net (code "77") (name "unconnected-(IC1B-PE8-Pad59)") (class "Default")
      (node (ref "IC1") (pin "59") (pinfunction "PE8_59") (pintype "bidirectional"))
    )
    (net (code "78") (name "unconnected-(IC1B-PE10-Pad63)") (class "Default")
      (node (ref "IC1") (pin "63") (pinfunction "PE10_63") (pintype "bidirectional"))
    )
    (net (code "79") (name "unconnected-(IC1B-PE11-Pad64)") (class "Default")
      (node (ref "IC1") (pin "64") (pinfunction "PE11_64") (pintype "bidirectional"))
    )
    (net (code "80") (name "unconnected-(IC1B-PE13-Pad66)") (class "Default")
      (node (ref "IC1") (pin "66") (pinfunction "PE13_66") (pintype "bidirectional"))
    )
    (net (code "81") (name "unconnected-(IC1B-PE14-Pad67)") (class "Default")
      (node (ref "IC1") (pin "67") (pinfunction "PE14_67") (pintype "bidirectional"))
    )
    (net (code "82") (name "unconnected-(IC1B-PE15-Pad68)") (class "Default")
      (node (ref "IC1") (pin "68") (pinfunction "PE15_68") (pintype "bidirectional"))
    )
    (net (code "83") (name "unconnected-(IC1B-PF0-Pad10)") (class "Default")
      (node (ref "IC1") (pin "10") (pinfunction "PF0_10") (pintype "bidirectional"))
    )
    (net (code "84") (name "unconnected-(IC1B-PF1-Pad11)") (class "Default")
      (node (ref "IC1") (pin "11") (pinfunction "PF1_11") (pintype "bidirectional"))
    )
    (net (code "85") (name "unconnected-(IC1B-PF2-Pad12)") (class "Default")
      (node (ref "IC1") (pin "12") (pinfunction "PF2_12") (pintype "bidirectional"))
    )
    (net (code "86") (name "unconnected-(IC1B-PF3-Pad13)") (class "Default")
      (node (ref "IC1") (pin "13") (pinfunction "PF3_13") (pintype "bidirectional"))
    )
    (net (code "87") (name "unconnected-(IC1B-PF4-Pad14)") (class "Default")
      (node (ref "IC1") (pin "14") (pinfunction "PF4_14") (pintype "bidirectional"))
    )
    (net (code "88") (name "unconnected-(IC1B-PF5-Pad15)") (class "Default")
      (node (ref "IC1") (pin "15") (pinfunction "PF5_15") (pintype "bidirectional"))
    )
    (net (code "89") (name "unconnected-(IC1B-PF6-Pad18)") (class "Default")
      (node (ref "IC1") (pin "18") (pinfunction "PF6_18") (pintype "bidirectional"))
    )
    (net (code "90") (name "unconnected-(IC1B-PF7-Pad19)") (class "Default")
      (node (ref "IC1") (pin "19") (pinfunction "PF7_19") (pintype "bidirectional"))
    )
    (net (code "91") (name "unconnected-(IC1B-PF8-Pad20)") (class "Default")
      (node (ref "IC1") (pin "20") (pinfunction "PF8_20") (pintype "bidirectional"))
    )
    (net (code "92") (name "unconnected-(IC1B-PF9-Pad21)") (class "Default")
      (node (ref "IC1") (pin "21") (pinfunction "PF9_21") (pintype "bidirectional"))
    )
    (net (code "93") (name "unconnected-(IC1B-PF10-Pad22)") (class "Default")
      (node (ref "IC1") (pin "22") (pinfunction "PF10_22") (pintype "bidirectional"))
    )
    (net (code "94") (name "unconnected-(IC1B-PF11-Pad49)") (class "Default")
      (node (ref "IC1") (pin "49") (pinfunction "PF11_49") (pintype "bidirectional"))
    )
    (net (code "95") (name "unconnected-(IC1B-PF12-Pad50)") (class "Default")
      (node (ref "IC1") (pin "50") (pinfunction "PF12_50") (pintype "bidirectional"))
    )
    (net (code "96") (name "unconnected-(IC1B-PF13-Pad53)") (class "Default")
      (node (ref "IC1") (pin "53") (pinfunction "PF13_53") (pintype "bidirectional"))
    )
    (net (code "97") (name "unconnected-(IC1B-PF14-Pad54)") (class "Default")
      (node (ref "IC1") (pin "54") (pinfunction "PF14_54") (pintype "bidirectional"))
    )
    (net (code "98") (name "unconnected-(IC1B-PF15-Pad55)") (class "Default")
      (node (ref "IC1") (pin "55") (pinfunction "PF15_55") (pintype "bidirectional"))
    )
    (net (code "99") (name "unconnected-(IC1B-PG0-Pad56)") (class "Default")
      (node (ref "IC1") (pin "56") (pinfunction "PG0_56") (pintype "bidirectional"))
    )
    (net (code "100") (name "unconnected-(IC1B-PG1-Pad57)") (class "Default")
      (node (ref "IC1") (pin "57") (pinfunction "PG1_57") (pintype "bidirectional"))
    )
    (net (code "101") (name "unconnected-(IC1C-PA8-Pad100)") (class "Default")
      (node (ref "IC1") (pin "100") (pinfunction "PA8_100") (pintype "bidirectional"))
    )
    (net (code "102") (name "unconnected-(IC1C-PA12-Pad104)") (class "Default")
      (node (ref "IC1") (pin "104") (pinfunction "PA12_104") (pintype "bidirectional"))
    )
    (net (code "103") (name "unconnected-(IC1C-PB5-Pad135)") (class "Default")
      (node (ref "IC1") (pin "135") (pinfunction "PB5_135") (pintype "bidirectional"))
    )
    (net (code "104") (name "unconnected-(IC1C-PB6-Pad136)") (class "Default")
      (node (ref "IC1") (pin "136") (pinfunction "PB6_136") (pintype "bidirectional"))
    )
    (net (code "105") (name "unconnected-(IC1C-PB13-Pad74)") (class "Default")
      (node (ref "IC1") (pin "74") (pinfunction "PB13_74") (pintype "bidirectional"))
    )
    (net (code "106") (name "unconnected-(IC1C-PB15-Pad76)") (class "Default")
      (node (ref "IC1") (pin "76") (pinfunction "PB15_76") (pintype "bidirectional"))
    )
    (net (code "107") (name "unconnected-(IC1C-PC8-Pad98)") (class "Default")
      (node (ref "IC1") (pin "98") (pinfunction "PC8_98") (pintype "bidirectional"))
    )
    (net (code "108") (name "unconnected-(IC1C-PC10-Pad111)") (class "Default")
      (node (ref "IC1") (pin "111") (pinfunction "PC10_111") (pintype "bidirectional"))
    )
    (net (code "109") (name "unconnected-(IC1C-PC11-Pad112)") (class "Default")
      (node (ref "IC1") (pin "112") (pinfunction "PC11_112") (pintype "bidirectional"))
    )
    (net (code "110") (name "unconnected-(IC1C-PC12-Pad113)") (class "Default")
      (node (ref "IC1") (pin "113") (pinfunction "PC12_113") (pintype "bidirectional"))
    )
    (net (code "111") (name "unconnected-(IC1C-PD0-Pad114)") (class "Default")
      (node (ref "IC1") (pin "114") (pinfunction "PD0_114") (pintype "bidirectional"))
    )
    (net (code "112") (name "unconnected-(IC1C-PD1-Pad115)") (class "Default")
      (node (ref "IC1") (pin "115") (pinfunction "PD1_115") (pintype "bidirectional"))
    )
    (net (code "113") (name "unconnected-(IC1C-PD2-Pad116)") (class "Default")
      (node (ref "IC1") (pin "116") (pinfunction "PD2_116") (pintype "bidirectional"))
    )
    (net (code "114") (name "unconnected-(IC1C-PD4-Pad118)") (class "Default")
      (node (ref "IC1") (pin "118") (pinfunction "PD4_118") (pintype "bidirectional"))
    )
    (net (code "115") (name "unconnected-(IC1C-PD5-Pad119)") (class "Default")
      (node (ref "IC1") (pin "119") (pinfunction "PD5_119") (pintype "bidirectional"))
    )
    (net (code "116") (name "unconnected-(IC1C-PD6-Pad122)") (class "Default")
      (node (ref "IC1") (pin "122") (pinfunction "PD6_122") (pintype "bidirectional"))
    )
    (net (code "117") (name "unconnected-(IC1C-PD7-Pad123)") (class "Default")
      (node (ref "IC1") (pin "123") (pinfunction "PD7_123") (pintype "bidirectional"))
    )
    (net (code "118") (name "unconnected-(IC1C-PD8-Pad77)") (class "Default")
      (node (ref "IC1") (pin "77") (pinfunction "PD8_77") (pintype "bidirectional"))
    )
    (net (code "119") (name "unconnected-(IC1C-PD9-Pad78)") (class "Default")
      (node (ref "IC1") (pin "78") (pinfunction "PD9_78") (pintype "bidirectional"))
    )
    (net (code "120") (name "unconnected-(IC1C-PD10-Pad79)") (class "Default")
      (node (ref "IC1") (pin "79") (pinfunction "PD10_79") (pintype "bidirectional"))
    )
    (net (code "121") (name "unconnected-(IC1C-PD11-Pad80)") (class "Default")
      (node (ref "IC1") (pin "80") (pinfunction "PD11_80") (pintype "bidirectional"))
    )
    (net (code "122") (name "unconnected-(IC1C-PD14-Pad85)") (class "Default")
      (node (ref "IC1") (pin "85") (pinfunction "PD14_85") (pintype "bidirectional"))
    )
    (net (code "123") (name "unconnected-(IC1C-PD15-Pad86)") (class "Default")
      (node (ref "IC1") (pin "86") (pinfunction "PD15_86") (pintype "bidirectional"))
    )
    (net (code "124") (name "unconnected-(IC1C-PE1-Pad142)") (class "Default")
      (node (ref "IC1") (pin "142") (pinfunction "PE1_142") (pintype "bidirectional"))
    )
    (net (code "125") (name "unconnected-(IC1C-PG5-Pad90)") (class "Default")
      (node (ref "IC1") (pin "90") (pinfunction "PG5_90") (pintype "bidirectional"))
    )
    (net (code "126") (name "unconnected-(IC1C-PG6-Pad91)") (class "Default")
      (node (ref "IC1") (pin "91") (pinfunction "PG6_91") (pintype "bidirectional"))
    )
    (net (code "127") (name "unconnected-(IC1C-PG9-Pad124)") (class "Default")
      (node (ref "IC1") (pin "124") (pinfunction "PG9_124") (pintype "bidirectional"))
    )
    (net (code "128") (name "unconnected-(IC1C-PG10-Pad125)") (class "Default")
      (node (ref "IC1") (pin "125") (pinfunction "PG10_125") (pintype "bidirectional"))
    )
    (net (code "129") (name "unconnected-(IC1C-PG11-Pad126)") (class "Default")
      (node (ref "IC1") (pin "126") (pinfunction "PG11_126") (pintype "bidirectional"))
    )
    (net (code "130") (name "unconnected-(IC1C-PG12-Pad127)") (class "Default")
      (node (ref "IC1") (pin "127") (pinfunction "PG12_127") (pintype "bidirectional"))
    )
    (net (code "131") (name "unconnected-(IC1C-PG13-Pad128)") (class "Default")
      (node (ref "IC1") (pin "128") (pinfunction "PG13_128") (pintype "bidirectional"))
    )
    (net (code "132") (name "unconnected-(IC1C-PG14-Pad129)") (class "Default")
      (node (ref "IC1") (pin "129") (pinfunction "PG14_129") (pintype "bidirectional"))
    )
    (net (code "133") (name "unconnected-(IC1C-PG15-Pad132)") (class "Default")
      (node (ref "IC1") (pin "132") (pinfunction "PG15_132") (pintype "bidirectional"))
    )
    (net (code "134") (name "unconnected-(J1-ID-Pad4)") (class "Default")
      (node (ref "J1") (pin "4") (pinfunction "ID_4") (pintype "bidirectional"))
    )
    (net (code "135") (name "unconnected-(JP1-Pad9)") (class "Default")
      (node (ref "JP1") (pin "9") (pinfunction "9_9") (pintype "passive"))
    )
    (net (code "136") (name "unconnected-(JP2-Pad9)") (class "Default")
      (node (ref "JP2") (pin "9") (pinfunction "9_9") (pintype "passive"))
    )
    (net (code "137") (name "unconnected-(JP3-Pad5)") (class "Default")
      (node (ref "JP3") (pin "5") (pinfunction "5_5") (pintype "passive"))
    )
    (net (code "138") (name "unconnected-(U1-P03{slash}AIN1-Pad6)") (class "Default")
      (node (ref "U1") (pin "6") (pinfunction "P03/AIN1_6") (pintype "bidirectional"))
    )
    (net (code "139") (name "unconnected-(U1-P009{slash}NFC1-Pad7)") (class "Default")
      (node (ref "U1") (pin "7") (pinfunction "P009/NFC1_7") (pintype "bidirectional"))
    )
    (net (code "140") (name "unconnected-(U1-P010{slash}NFC2-Pad8)") (class "Default")
      (node (ref "U1") (pin "8") (pinfunction "P010/NFC2_8") (pintype "bidirectional"))
    )
    (net (code "141") (name "unconnected-(U1-P18-Pad12)") (class "Default")
      (node (ref "U1") (pin "12") (pinfunction "P18_12") (pintype "bidirectional"))
    )
    (net (code "142") (name "unconnected-(U1-P20-Pad13)") (class "Default")
      (node (ref "U1") (pin "13") (pinfunction "P20_13") (pintype "bidirectional"))
    )
    (net (code "143") (name "unconnected-(U1-P21{slash}RESET-Pad14)") (class "Default")
      (node (ref "U1") (pin "14") (pinfunction "P21/RESET_14") (pintype "bidirectional"))
    )
    (net (code "144") (name "unconnected-(U2-NC-Pad1)") (class "Default")
      (node (ref "U2") (pin "1") (pinfunction "NC_1") (pintype "bidirectional"))
    )
    (net (code "145") (name "unconnected-(U2-PadCD1)") (class "Default")
      (node (ref "U2") (pin "CD1") (pinfunction "CD1_CD1") (pintype "bidirectional"))
    )
    (net (code "146") (name "unconnected-(U2-RSV-Pad8)") (class "Default")
      (node (ref "U2") (pin "8") (pinfunction "RSV_8") (pintype "bidirectional"))
    )
    (net (code "147") (name "~{CS_SD}") (class "Default")
      (node (ref "IC1") (pin "65") (pinfunction "PE12_65") (pintype "bidirectional"))
      (node (ref "U2") (pin "2") (pinfunction "CS_2") (pintype "bidirectional"))
    )
    (net (code "148") (name "~{SD_ENABLE}") (class "Default")
      (node (ref "IC1") (pin "73") (pinfunction "PB12_73") (pintype "bidirectional"))
      (node (ref "Q3") (pin "P1") (pinfunction "G_P1") (pintype "passive"))
      (node (ref "R11") (pin "1") (pinfunction "1_1") (pintype "passive"))
    )
  )
)
